# GUVB-C31SM_BB.net
KiCad netlist of a schematic drawn in Altium Designer
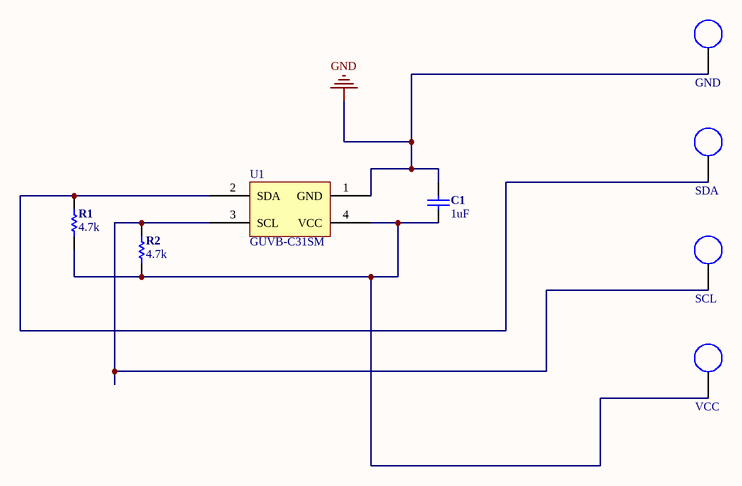
[diagram p0: GUVB-C31SM_BB.SchDoc]

(export (version "E")
  (design (tool "Eeschema 10.0.6"))
  (components
    (comp (ref "C1")
      (value "1uF")
      (footprint "CAP-0805(2012)-R")
      (description "___ OHM ___ mW 0805(2012) SMD")
      (libsource (lib "UVS-Schlib") (part "C-0805(2012)"))
    )
    (comp (ref "GND")
      (value "S1751-46R")
      (footprint "S1751-46R")
      (description "PC TEST POINT TIN SMD")
      (fields (field (name "MANUFACTURER") "Harwin Inc."))
      (libsource (lib "UVS-Schlib") (part "S1751-46R"))
    )
    (comp (ref "R1")
      (value "4.7k")
      (footprint "R-0805(2012)-R")
      (description "___ OHM ___ mW 0805(2012) SMD")
      (libsource (lib "UVS-Schlib") (part "R-0805(2012)"))
    )
    (comp (ref "R2")
      (value "4.7k")
      (footprint "R-0805(2012)-R")
      (description "___ OHM ___ mW 0805(2012) SMD")
      (libsource (lib "UVS-Schlib") (part "R-0805(2012)"))
    )
    (comp (ref "SCL")
      (value "S1751-46R")
      (footprint "S1751-46R")
      (description "PC TEST POINT TIN SMD")
      (fields (field (name "MANUFACTURER") "Harwin Inc."))
      (libsource (lib "UVS-Schlib") (part "S1751-46R"))
    )
    (comp (ref "SDA")
      (value "S1751-46R")
      (footprint "S1751-46R")
      (description "PC TEST POINT TIN SMD")
      (fields (field (name "MANUFACTURER") "Harwin Inc."))
      (libsource (lib "UVS-Schlib") (part "S1751-46R"))
    )
    (comp (ref "U1")
      (value "GUVB-C31SM")
      (footprint "GUVB-C31SM")
      (libsource (lib "UVS-Schlib") (part "GUVB-C31SM"))
    )
    (comp (ref "VCC")
      (value "S1751-46R")
      (footprint "S1751-46R")
      (description "PC TEST POINT TIN SMD")
      (fields (field (name "MANUFACTURER") "Harwin Inc."))
      (libsource (lib "UVS-Schlib") (part "S1751-46R"))
    )
  )
  (nets
    (net (code "1") (name "GND") (class "Default")
      (node (ref "C1") (pin "1") (pinfunction "1_1") (pintype "passive"))
      (node (ref "GND") (pin "1") (pinfunction "1_1") (pintype "passive"))
      (node (ref "U1") (pin "1") (pinfunction "GND_1") (pintype "passive"))
    )
    (net (code "2") (name "Net-(U1-SCL)") (class "Default")
      (node (ref "R2") (pin "1") (pinfunction "1_1") (pintype "passive"))
      (node (ref "SCL") (pin "1") (pinfunction "1_1") (pintype "passive"))
      (node (ref "U1") (pin "3") (pinfunction "SCL_3") (pintype "passive"))
    )
    (net (code "3") (name "Net-(U1-SDA)") (class "Default")
      (node (ref "R1") (pin "1") (pinfunction "1_1") (pintype "passive"))
      (node (ref "SDA") (pin "1") (pinfunction "1_1") (pintype "passive"))
      (node (ref "U1") (pin "2") (pinfunction "SDA_2") (pintype "passive"))
    )
    (net (code "4") (name "Net-(U1-VCC)") (class "Default")
      (node (ref "C1") (pin "2") (pinfunction "2_2") (pintype "passive"))
      (node (ref "R1") (pin "2") (pinfunction "2_2") (pintype "passive"))
      (node (ref "R2") (pin "2") (pinfunction "2_2") (pintype "passive"))
      (node (ref "U1") (pin "4") (pinfunction "VCC_4") (pintype "passive"))
      (node (ref "VCC") (pin "1") (pinfunction "1_1") (pintype "passive"))
    )
  )
)
